# neopixel_nano_strip.net
KiCad netlist of a schematic drawn in EAGLE
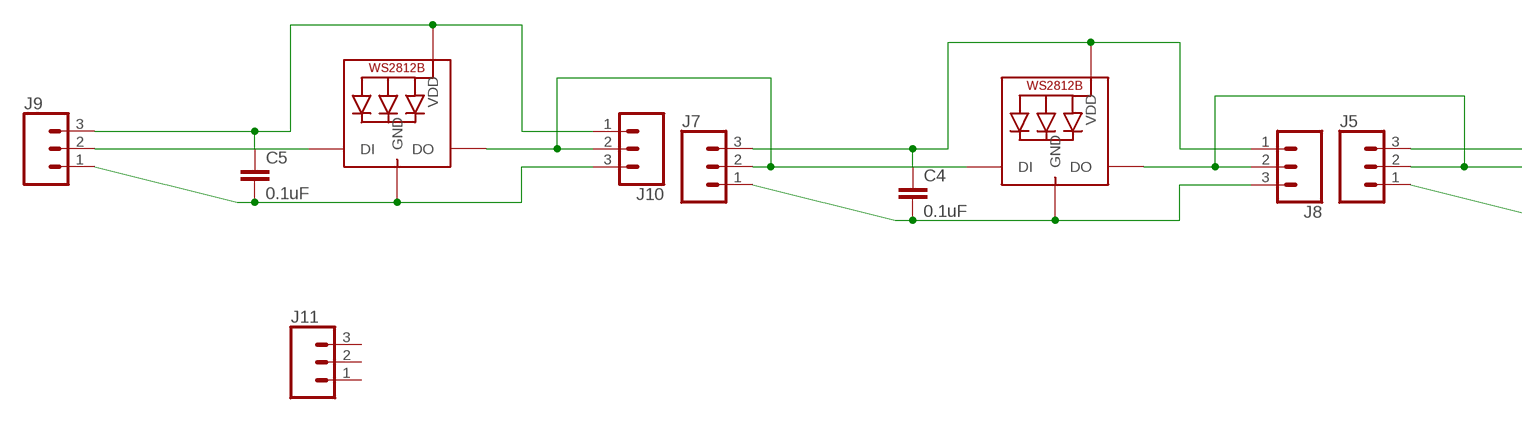
[diagram p0: schematic, sheet 1, part 1 of 2]
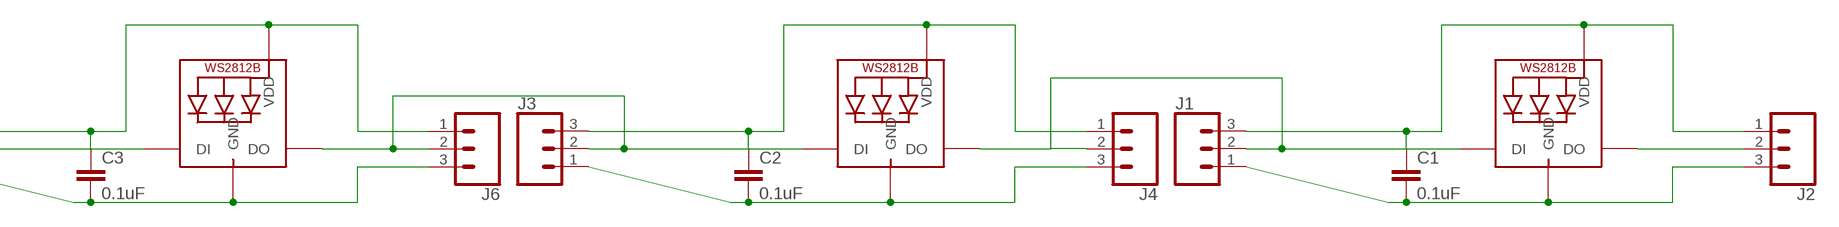
[diagram p1: schematic, sheet 1, part 2 of 2]

(export (version "E")
  (design (tool "Eeschema 10.0.6"))
  (components
    (comp (ref "C1")
      (value "0.1uF")
      (footprint "eagle-import:0603")
      (libsource (lib "eagle-import") (part "0.1UF-0603-25V-(+80/-20%)"))
    )
    (comp (ref "C2")
      (value "0.1uF")
      (footprint "eagle-import:0603")
      (libsource (lib "eagle-import") (part "0.1UF-0603-25V-(+80/-20%)"))
    )
    (comp (ref "C3")
      (value "0.1uF")
      (footprint "eagle-import:0603")
      (libsource (lib "eagle-import") (part "0.1UF-0603-25V-(+80/-20%)"))
    )
    (comp (ref "C4")
      (value "0.1uF")
      (footprint "eagle-import:0603")
      (libsource (lib "eagle-import") (part "0.1UF-0603-25V-(+80/-20%)"))
    )
    (comp (ref "C5")
      (value "0.1uF")
      (footprint "eagle-import:0603")
      (libsource (lib "eagle-import") (part "0.1UF-0603-25V-(+80/-20%)"))
    )
    (comp (ref "J1")
      (value "CONN_031X03_NO_SILK")
      (footprint "eagle-import:1X03_NO_SILK")
      (libsource (lib "eagle-import") (part "CONN_031X03_NO_SILK"))
    )
    (comp (ref "J2")
      (value "CONN_031X03_NO_SILK")
      (footprint "eagle-import:1X03_NO_SILK")
      (libsource (lib "eagle-import") (part "CONN_031X03_NO_SILK"))
    )
    (comp (ref "J3")
      (value "CONN_031X03_NO_SILK")
      (footprint "eagle-import:1X03_NO_SILK")
      (libsource (lib "eagle-import") (part "CONN_031X03_NO_SILK"))
    )
    (comp (ref "J4")
      (value "CONN_031X03_NO_SILK")
      (footprint "eagle-import:1X03_NO_SILK")
      (libsource (lib "eagle-import") (part "CONN_031X03_NO_SILK"))
    )
    (comp (ref "J5")
      (value "CONN_031X03_NO_SILK")
      (footprint "eagle-import:1X03_NO_SILK")
      (libsource (lib "eagle-import") (part "CONN_031X03_NO_SILK"))
    )
    (comp (ref "J6")
      (value "CONN_031X03_NO_SILK")
      (footprint "eagle-import:1X03_NO_SILK")
      (libsource (lib "eagle-import") (part "CONN_031X03_NO_SILK"))
    )
    (comp (ref "J7")
      (value "CONN_031X03_NO_SILK")
      (footprint "eagle-import:1X03_NO_SILK")
      (libsource (lib "eagle-import") (part "CONN_031X03_NO_SILK"))
    )
    (comp (ref "J8")
      (value "CONN_031X03_NO_SILK")
      (footprint "eagle-import:1X03_NO_SILK")
      (libsource (lib "eagle-import") (part "CONN_031X03_NO_SILK"))
    )
    (comp (ref "J9")
      (value "CONN_031X03_NO_SILK")
      (footprint "eagle-import:1X03_NO_SILK")
      (libsource (lib "eagle-import") (part "CONN_031X03_NO_SILK"))
    )
    (comp (ref "J10")
      (value "CONN_031X03_NO_SILK")
      (footprint "eagle-import:1X03_NO_SILK")
      (libsource (lib "eagle-import") (part "CONN_031X03_NO_SILK"))
    )
    (comp (ref "J11")
      (value "CONN_031X03_NO_SILK")
      (footprint "eagle-import:1X03_NO_SILK")
      (libsource (lib "eagle-import") (part "CONN_031X03_NO_SILK"))
    )
    (comp (ref "LED1")
      (value "WS2812BNANO")
      (footprint "eagle-import:NEOPIXEL_NANO")
      (libsource (lib "eagle-import") (part "WS2812BNANO"))
    )
    (comp (ref "LED2")
      (value "WS2812BNANO")
      (footprint "eagle-import:NEOPIXEL_NANO")
      (libsource (lib "eagle-import") (part "WS2812BNANO"))
    )
    (comp (ref "LED3")
      (value "WS2812BNANO")
      (footprint "eagle-import:NEOPIXEL_NANO")
      (libsource (lib "eagle-import") (part "WS2812BNANO"))
    )
    (comp (ref "LED4")
      (value "WS2812BNANO")
      (footprint "eagle-import:NEOPIXEL_NANO")
      (libsource (lib "eagle-import") (part "WS2812BNANO"))
    )
    (comp (ref "LED5")
      (value "WS2812BNANO")
      (footprint "eagle-import:NEOPIXEL_NANO")
      (libsource (lib "eagle-import") (part "WS2812BNANO"))
    )
  )
  (nets
    (net (code "1") (name "/GND") (class "Default")
      (node (ref "C1") (pin "2") (pinfunction "2_2") (pintype "passive"))
      (node (ref "C2") (pin "2") (pinfunction "2_2") (pintype "passive"))
      (node (ref "C3") (pin "2") (pinfunction "2_2") (pintype "passive"))
      (node (ref "C4") (pin "2") (pinfunction "2_2") (pintype "passive"))
      (node (ref "C5") (pin "2") (pinfunction "2_2") (pintype "passive"))
      (node (ref "J1") (pin "1") (pinfunction "1_1") (pintype "passive"))
      (node (ref "J10") (pin "3") (pinfunction "3_3") (pintype "passive"))
      (node (ref "J2") (pin "3") (pinfunction "3_3") (pintype "passive"))
      (node (ref "J3") (pin "1") (pinfunction "1_1") (pintype "passive"))
      (node (ref "J4") (pin "3") (pinfunction "3_3") (pintype "passive"))
      (node (ref "J5") (pin "1") (pinfunction "1_1") (pintype "passive"))
      (node (ref "J6") (pin "3") (pinfunction "3_3") (pintype "passive"))
      (node (ref "J7") (pin "1") (pinfunction "1_1") (pintype "passive"))
      (node (ref "J8") (pin "3") (pinfunction "3_3") (pintype "passive"))
      (node (ref "J9") (pin "1") (pinfunction "1_1") (pintype "passive"))
      (node (ref "LED1") (pin "P$2") (pinfunction "GND_P$2") (pintype "power_in"))
      (node (ref "LED2") (pin "P$2") (pinfunction "GND_P$2") (pintype "power_in"))
      (node (ref "LED3") (pin "P$2") (pinfunction "GND_P$2") (pintype "power_in"))
      (node (ref "LED4") (pin "P$2") (pinfunction "GND_P$2") (pintype "power_in"))
      (node (ref "LED5") (pin "P$2") (pinfunction "GND_P$2") (pintype "power_in"))
    )
    (net (code "2") (name "/VCC") (class "Default")
      (node (ref "C1") (pin "1") (pinfunction "1_1") (pintype "passive"))
      (node (ref "C2") (pin "1") (pinfunction "1_1") (pintype "passive"))
      (node (ref "C3") (pin "1") (pinfunction "1_1") (pintype "passive"))
      (node (ref "C4") (pin "1") (pinfunction "1_1") (pintype "passive"))
      (node (ref "C5") (pin "1") (pinfunction "1_1") (pintype "passive"))
      (node (ref "J1") (pin "3") (pinfunction "3_3") (pintype "passive"))
      (node (ref "J10") (pin "1") (pinfunction "1_1") (pintype "passive"))
      (node (ref "J2") (pin "1") (pinfunction "1_1") (pintype "passive"))
      (node (ref "J3") (pin "3") (pinfunction "3_3") (pintype "passive"))
      (node (ref "J4") (pin "1") (pinfunction "1_1") (pintype "passive"))
      (node (ref "J5") (pin "3") (pinfunction "3_3") (pintype "passive"))
      (node (ref "J6") (pin "1") (pinfunction "1_1") (pintype "passive"))
      (node (ref "J7") (pin "3") (pinfunction "3_3") (pintype "passive"))
      (node (ref "J8") (pin "1") (pinfunction "1_1") (pintype "passive"))
      (node (ref "J9") (pin "3") (pinfunction "3_3") (pintype "passive"))
      (node (ref "LED1") (pin "P$4") (pinfunction "VDD_P$4") (pintype "power_in"))
      (node (ref "LED2") (pin "P$4") (pinfunction "VDD_P$4") (pintype "power_in"))
      (node (ref "LED3") (pin "P$4") (pinfunction "VDD_P$4") (pintype "power_in"))
      (node (ref "LED4") (pin "P$4") (pinfunction "VDD_P$4") (pintype "power_in"))
      (node (ref "LED5") (pin "P$4") (pinfunction "VDD_P$4") (pintype "power_in"))
    )
    (net (code "3") (name "Net-(LED1-DI)") (class "Default")
      (node (ref "J1") (pin "2") (pinfunction "2_2") (pintype "passive"))
      (node (ref "J4") (pin "2") (pinfunction "2_2") (pintype "passive"))
      (node (ref "LED1") (pin "P$3") (pinfunction "DI_P$3") (pintype "input"))
      (node (ref "LED2") (pin "P$1") (pinfunction "DO_P$1") (pintype "output"))
    )
    (net (code "4") (name "Net-(LED1-DO)") (class "Default")
      (node (ref "J2") (pin "2") (pinfunction "2_2") (pintype "passive"))
      (node (ref "LED1") (pin "P$1") (pinfunction "DO_P$1") (pintype "output"))
    )
    (net (code "5") (name "Net-(LED2-DI)") (class "Default")
      (node (ref "J3") (pin "2") (pinfunction "2_2") (pintype "passive"))
      (node (ref "J6") (pin "2") (pinfunction "2_2") (pintype "passive"))
      (node (ref "LED2") (pin "P$3") (pinfunction "DI_P$3") (pintype "input"))
      (node (ref "LED3") (pin "P$1") (pinfunction "DO_P$1") (pintype "output"))
    )
    (net (code "6") (name "Net-(LED3-DI)") (class "Default")
      (node (ref "J5") (pin "2") (pinfunction "2_2") (pintype "passive"))
      (node (ref "J8") (pin "2") (pinfunction "2_2") (pintype "passive"))
      (node (ref "LED3") (pin "P$3") (pinfunction "DI_P$3") (pintype "input"))
      (node (ref "LED4") (pin "P$1") (pinfunction "DO_P$1") (pintype "output"))
    )
    (net (code "7") (name "Net-(LED4-DI)") (class "Default")
      (node (ref "J10") (pin "2") (pinfunction "2_2") (pintype "passive"))
      (node (ref "J7") (pin "2") (pinfunction "2_2") (pintype "passive"))
      (node (ref "LED4") (pin "P$3") (pinfunction "DI_P$3") (pintype "input"))
      (node (ref "LED5") (pin "P$1") (pinfunction "DO_P$1") (pintype "output"))
    )
    (net (code "8") (name "Net-(LED5-DI)") (class "Default")
      (node (ref "J9") (pin "2") (pinfunction "2_2") (pintype "passive"))
      (node (ref "LED5") (pin "P$3") (pinfunction "DI_P$3") (pintype "input"))
    )
    (net (code "9") (name "unconnected-(J11-Pad1)") (class "Default")
      (node (ref "J11") (pin "1") (pinfunction "1_1") (pintype "passive"))
    )
    (net (code "10") (name "unconnected-(J11-Pad2)") (class "Default")
      (node (ref "J11") (pin "2") (pinfunction "2_2") (pintype "passive"))
    )
    (net (code "11") (name "unconnected-(J11-Pad3)") (class "Default")
      (node (ref "J11") (pin "3") (pinfunction "3_3") (pintype "passive"))
    )
  )
)
